# fDrive_RP2040.net
KiCad netlist of a schematic drawn in EAGLE
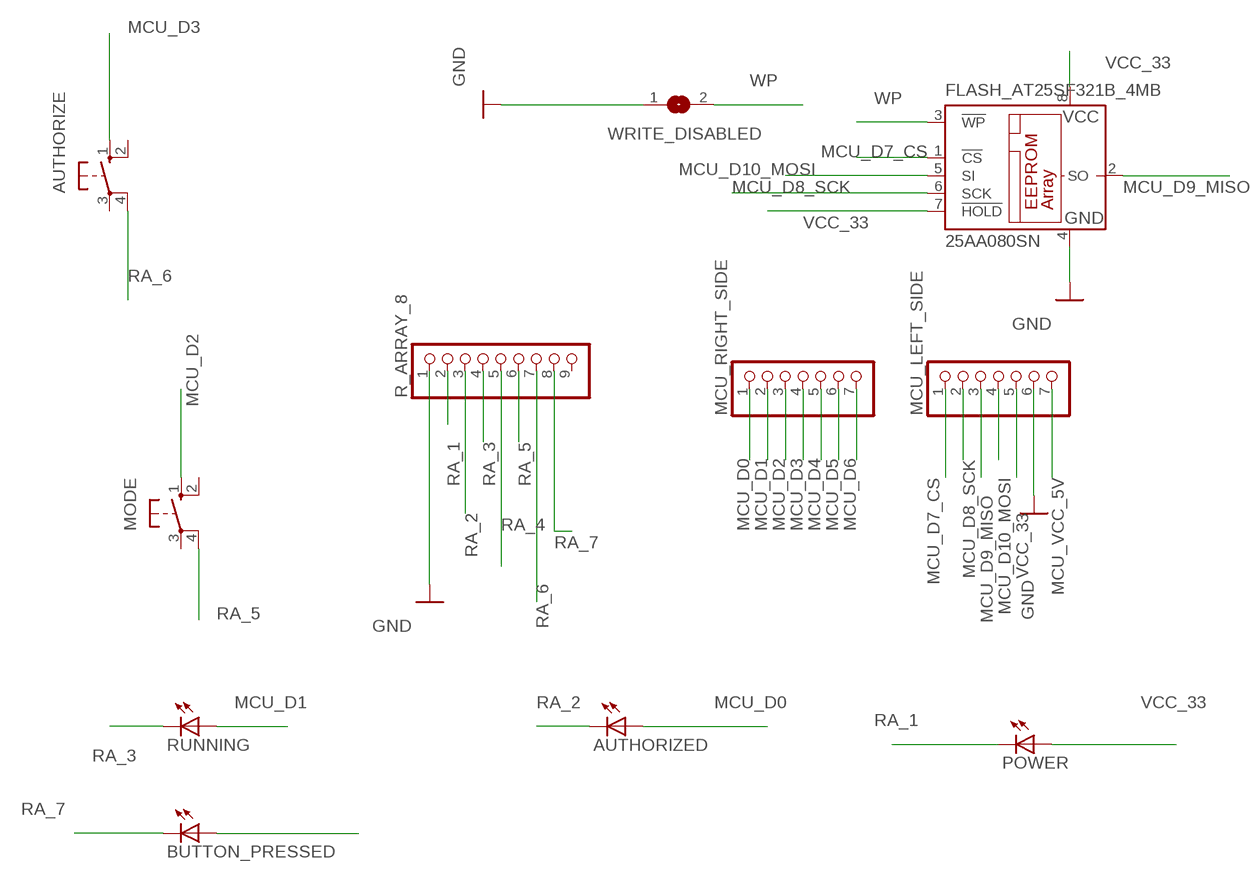
[diagram p0: schematic, sheet 1]

(export (version "E")
  (design (tool "Eeschema 10.0.6"))
  (components
    (comp (ref "AUTHORIZE")
      (value "10-XX")
      (footprint "eagle-import:B3F-10XX")
      (fields (field (name "MPN") "B3F-1000"))
      (libsource (lib "eagle-import") (part "10-XX"))
    )
    (comp (ref "AUTHORIZED")
      (value "LEDSMT1206")
      (footprint "eagle-import:1206")
      (libsource (lib "eagle-import") (part "LEDSMT1206"))
    )
    (comp (ref "BUTTON_PRESSED")
      (value "LEDSMT1206")
      (footprint "eagle-import:1206")
      (libsource (lib "eagle-import") (part "LEDSMT1206"))
    )
    (comp (ref "FLASH_AT25SF321B_4MB")
      (value "25AA080SN")
      (footprint "eagle-import:SO-08")
      (fields (field (name "MF") "MICROCHIP") (field (name "MPN") "25AA080/SN"))
      (libsource (lib "eagle-import") (part "25SNAA080"))
    )
    (comp (ref "MCU_LEFT_SIDE")
      (value "PINHD-1X7")
      (footprint "eagle-import:1X07")
      (libsource (lib "eagle-import") (part "PINHD-1X7"))
    )
    (comp (ref "MCU_RIGHT_SIDE")
      (value "PINHD-1X7")
      (footprint "eagle-import:1X07")
      (libsource (lib "eagle-import") (part "PINHD-1X7"))
    )
    (comp (ref "MODE")
      (value "10-XX")
      (footprint "eagle-import:B3F-10XX")
      (fields (field (name "MPN") "B3F-1000"))
      (libsource (lib "eagle-import") (part "10-XX"))
    )
    (comp (ref "POWER")
      (value "LEDSMT1206")
      (footprint "eagle-import:1206")
      (libsource (lib "eagle-import") (part "LEDSMT1206"))
    )
    (comp (ref "RUNNING")
      (value "LEDSMT1206")
      (footprint "eagle-import:1206")
      (libsource (lib "eagle-import") (part "LEDSMT1206"))
    )
    (comp (ref "R_ARRAY_8")
      (value "PINHD-1X9")
      (footprint "eagle-import:1X09-BIG")
      (libsource (lib "eagle-import") (part "PINHD-1X9"))
    )
    (comp (ref "WRITE_DISABLED")
      (value "SOLDERJUMPER")
      (footprint "eagle-import:SOLDERJUMPER_ARROW_NOPASTE")
      (libsource (lib "eagle-import") (part "SOLDERJUMPER"))
    )
  )
  (nets
    (net (code "1") (name "/MCU_D0") (class "Default")
      (node (ref "AUTHORIZED") (pin "A") (pinfunction "A_A") (pintype "passive"))
      (node (ref "MCU_RIGHT_SIDE") (pin "1") (pinfunction "1_1") (pintype "passive"))
    )
    (net (code "2") (name "/MCU_D1") (class "Default")
      (node (ref "MCU_RIGHT_SIDE") (pin "2") (pinfunction "2_2") (pintype "passive"))
      (node (ref "RUNNING") (pin "A") (pinfunction "A_A") (pintype "passive"))
    )
    (net (code "3") (name "/MCU_D2") (class "Default")
      (node (ref "MCU_RIGHT_SIDE") (pin "3") (pinfunction "3_3") (pintype "passive"))
      (node (ref "MODE") (pin "1") (pinfunction "S_1") (pintype "passive"))
    )
    (net (code "4") (name "/MCU_D3") (class "Default")
      (node (ref "AUTHORIZE") (pin "1") (pinfunction "S_1") (pintype "passive"))
      (node (ref "MCU_RIGHT_SIDE") (pin "4") (pinfunction "4_4") (pintype "passive"))
    )
    (net (code "5") (name "/MCU_D4") (class "Default")
      (node (ref "BUTTON_PRESSED") (pin "A") (pinfunction "A_A") (pintype "passive"))
      (node (ref "MCU_RIGHT_SIDE") (pin "5") (pinfunction "5_5") (pintype "passive"))
    )
    (net (code "6") (name "/MCU_D5") (class "Default")
      (node (ref "MCU_RIGHT_SIDE") (pin "6") (pinfunction "6_6") (pintype "passive"))
    )
    (net (code "7") (name "/MCU_D6") (class "Default")
      (node (ref "MCU_RIGHT_SIDE") (pin "7") (pinfunction "7_7") (pintype "passive"))
    )
    (net (code "8") (name "/MCU_D7_CS") (class "Default")
      (node (ref "FLASH_AT25SF321B_4MB") (pin "1") (pinfunction "~{CS}_1") (pintype "input"))
      (node (ref "MCU_LEFT_SIDE") (pin "1") (pinfunction "1_1") (pintype "passive"))
    )
    (net (code "9") (name "/MCU_D8_SCK") (class "Default")
      (node (ref "FLASH_AT25SF321B_4MB") (pin "6") (pinfunction "SCK_6") (pintype "input"))
      (node (ref "MCU_LEFT_SIDE") (pin "2") (pinfunction "2_2") (pintype "passive"))
    )
    (net (code "10") (name "/MCU_D9_MISO") (class "Default")
      (node (ref "FLASH_AT25SF321B_4MB") (pin "2") (pinfunction "SO_2") (pintype "bidirectional"))
      (node (ref "MCU_LEFT_SIDE") (pin "3") (pinfunction "3_3") (pintype "passive"))
    )
    (net (code "11") (name "/MCU_D10_MOSI") (class "Default")
      (node (ref "FLASH_AT25SF321B_4MB") (pin "5") (pinfunction "SI_5") (pintype "input"))
      (node (ref "MCU_LEFT_SIDE") (pin "4") (pinfunction "4_4") (pintype "passive"))
    )
    (net (code "12") (name "/MCU_VCC_5V") (class "Default")
      (node (ref "MCU_LEFT_SIDE") (pin "7") (pinfunction "7_7") (pintype "passive"))
    )
    (net (code "13") (name "/RA_1") (class "Default")
      (node (ref "POWER") (pin "C") (pinfunction "C_C") (pintype "passive"))
      (node (ref "R_ARRAY_8") (pin "2") (pinfunction "2_2") (pintype "passive"))
    )
    (net (code "14") (name "/RA_2") (class "Default")
      (node (ref "AUTHORIZED") (pin "C") (pinfunction "C_C") (pintype "passive"))
      (node (ref "R_ARRAY_8") (pin "3") (pinfunction "3_3") (pintype "passive"))
    )
    (net (code "15") (name "/RA_3") (class "Default")
      (node (ref "RUNNING") (pin "C") (pinfunction "C_C") (pintype "passive"))
      (node (ref "R_ARRAY_8") (pin "4") (pinfunction "4_4") (pintype "passive"))
    )
    (net (code "16") (name "/RA_4") (class "Default")
      (node (ref "R_ARRAY_8") (pin "5") (pinfunction "5_5") (pintype "passive"))
    )
    (net (code "17") (name "/RA_5") (class "Default")
      (node (ref "MODE") (pin "4") (pinfunction "P1_4") (pintype "passive"))
      (node (ref "R_ARRAY_8") (pin "6") (pinfunction "6_6") (pintype "passive"))
    )
    (net (code "18") (name "/RA_6") (class "Default")
      (node (ref "AUTHORIZE") (pin "4") (pinfunction "P1_4") (pintype "passive"))
      (node (ref "R_ARRAY_8") (pin "7") (pinfunction "7_7") (pintype "passive"))
    )
    (net (code "19") (name "/RA_7") (class "Default")
      (node (ref "BUTTON_PRESSED") (pin "C") (pinfunction "C_C") (pintype "passive"))
      (node (ref "R_ARRAY_8") (pin "8") (pinfunction "8_8") (pintype "passive"))
    )
    (net (code "20") (name "/VCC_33") (class "Default")
      (node (ref "FLASH_AT25SF321B_4MB") (pin "7") (pinfunction "~{HOLD}_7") (pintype "input"))
      (node (ref "FLASH_AT25SF321B_4MB") (pin "8") (pinfunction "VCC_8") (pintype "power_in"))
      (node (ref "MCU_LEFT_SIDE") (pin "5") (pinfunction "5_5") (pintype "passive"))
      (node (ref "POWER") (pin "A") (pinfunction "A_A") (pintype "passive"))
    )
    (net (code "21") (name "/WP") (class "Default")
      (node (ref "FLASH_AT25SF321B_4MB") (pin "3") (pinfunction "~{WP}_3") (pintype "input"))
      (node (ref "WRITE_DISABLED") (pin "2") (pinfunction "2_2") (pintype "passive"))
    )
    (net (code "22") (name "GND") (class "Default")
      (node (ref "FLASH_AT25SF321B_4MB") (pin "4") (pinfunction "GND_4") (pintype "power_in"))
      (node (ref "MCU_LEFT_SIDE") (pin "6") (pinfunction "6_6") (pintype "passive"))
      (node (ref "R_ARRAY_8") (pin "1") (pinfunction "1_1") (pintype "passive"))
      (node (ref "WRITE_DISABLED") (pin "1") (pinfunction "1_1") (pintype "passive"))
    )
    (net (code "23") (name "unconnected-(AUTHORIZE-P-Pad3)") (class "Default")
      (node (ref "AUTHORIZE") (pin "3") (pinfunction "P_3") (pintype "passive"))
    )
    (net (code "24") (name "unconnected-(AUTHORIZE-S1-Pad2)") (class "Default")
      (node (ref "AUTHORIZE") (pin "2") (pinfunction "S1_2") (pintype "passive"))
    )
    (net (code "25") (name "unconnected-(MODE-P-Pad3)") (class "Default")
      (node (ref "MODE") (pin "3") (pinfunction "P_3") (pintype "passive"))
    )
    (net (code "26") (name "unconnected-(MODE-S1-Pad2)") (class "Default")
      (node (ref "MODE") (pin "2") (pinfunction "S1_2") (pintype "passive"))
    )
    (net (code "27") (name "unconnected-(R_ARRAY_8-Pad9)") (class "Default")
      (node (ref "R_ARRAY_8") (pin "9") (pinfunction "9_9") (pintype "passive"))
    )
  )
)
